# Hooly_2_023.net
KiCad netlist of a schematic drawn in EAGLE
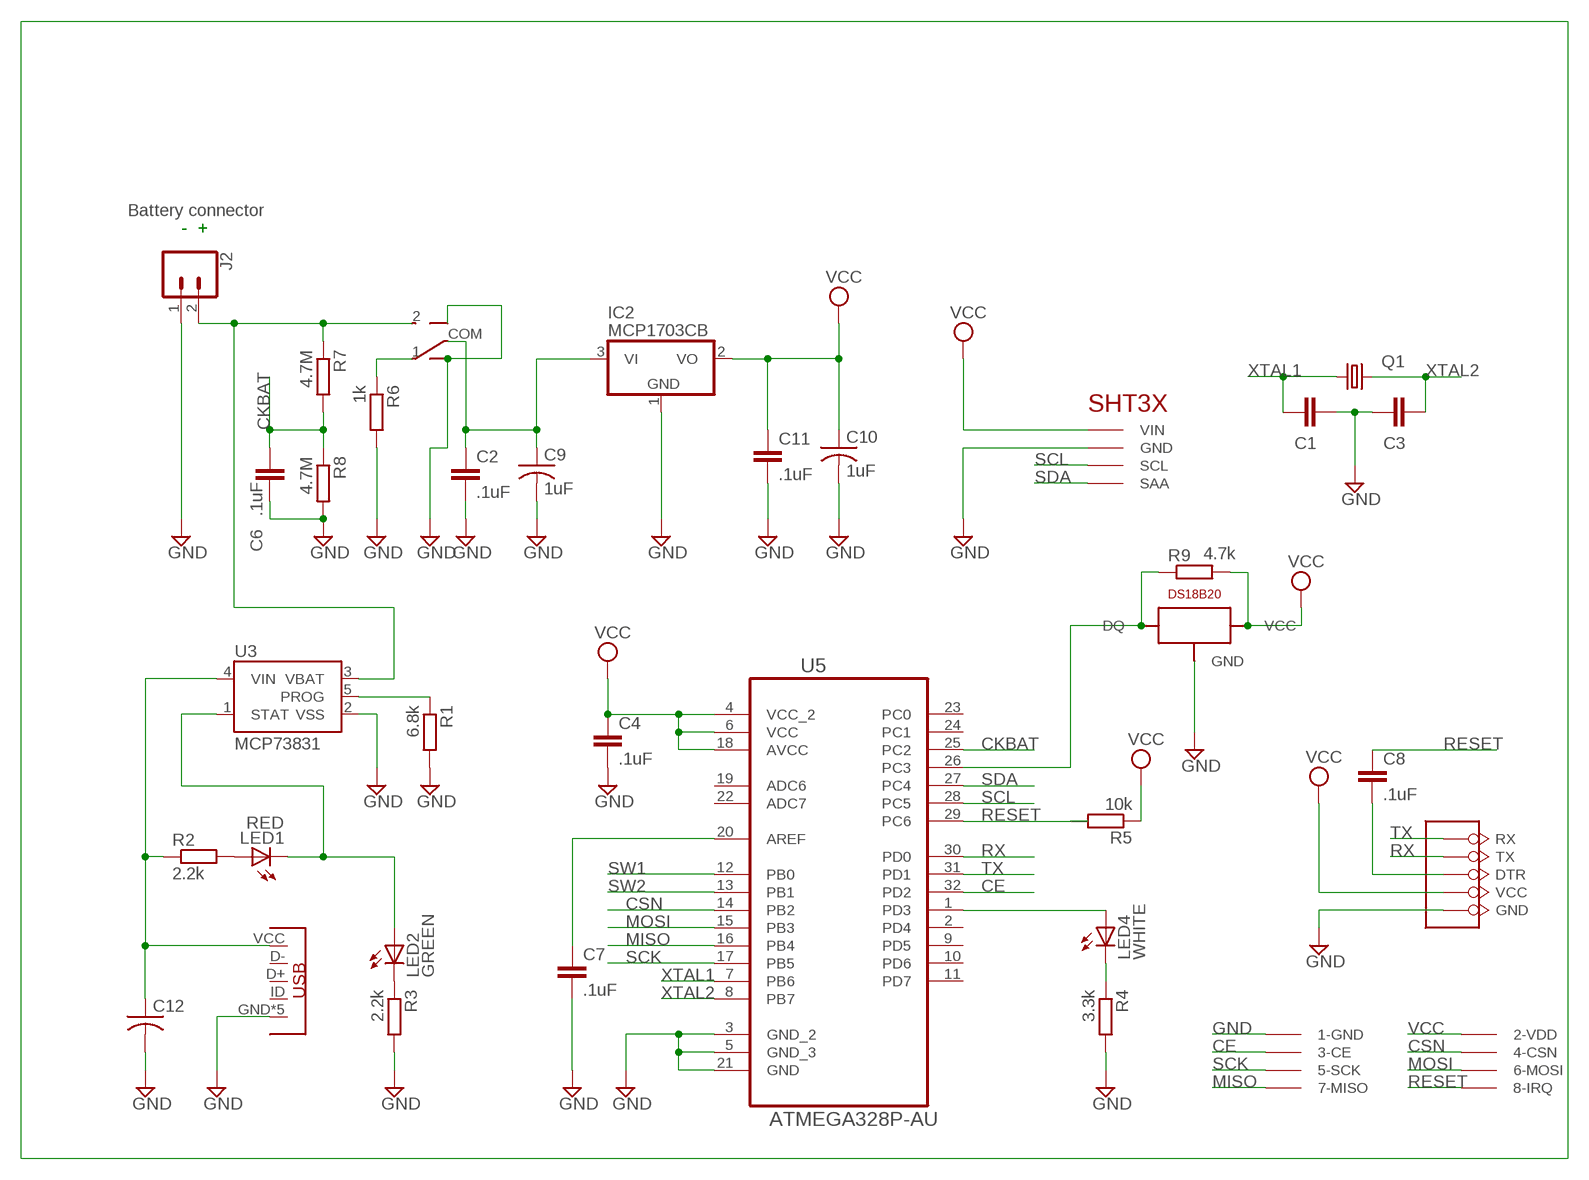
[diagram p0: schematic, sheet 1]

(export (version "E")
  (design (tool "Eeschema 10.0.6"))
  (components
    (comp (ref "C1")
      (value "C-EUC0603K")
      (footprint "eagle-import:C0603K")
      (libsource (lib "eagle-import") (part "C-EUC0603K"))
    )
    (comp (ref "C2")
      (value ".1uF")
      (footprint "eagle-import:C0603")
      (libsource (lib "eagle-import") (part "resistor_348_C-EUC0603"))
    )
    (comp (ref "C3")
      (value "C-EUC0603K")
      (footprint "eagle-import:C0603K")
      (libsource (lib "eagle-import") (part "C-EUC0603K"))
    )
    (comp (ref "C4")
      (value ".1uF")
      (footprint "eagle-import:C0603")
      (libsource (lib "eagle-import") (part "resistor_348_C-EUC0603"))
    )
    (comp (ref "C6")
      (value ".1uF")
      (footprint "eagle-import:C0603")
      (libsource (lib "eagle-import") (part "resistor_348_C-EUC0603"))
    )
    (comp (ref "C7")
      (value ".1uF")
      (footprint "eagle-import:C0603")
      (libsource (lib "eagle-import") (part "resistor_348_C-EUC0603"))
    )
    (comp (ref "C8")
      (value ".1uF")
      (footprint "eagle-import:C0603")
      (libsource (lib "eagle-import") (part "resistor_348_C-EUC0603"))
    )
    (comp (ref "C9")
      (value "1uF")
      (footprint "eagle-import:C1206K")
      (libsource (lib "eagle-import") (part "C-USC1206K"))
    )
    (comp (ref "C10")
      (value "1uF")
      (footprint "eagle-import:C1206K")
      (libsource (lib "eagle-import") (part "C-USC1206K"))
    )
    (comp (ref "C11")
      (value ".1uF")
      (footprint "eagle-import:C0603")
      (libsource (lib "eagle-import") (part "resistor_348_C-EUC0603"))
    )
    (comp (ref "C12")
      (value "C-USC1206K")
      (footprint "eagle-import:C1206K")
      (libsource (lib "eagle-import") (part "C-USC1206K"))
    )
    (comp (ref "IC2")
      (value "MCP1703CB")
      (footprint "eagle-import:SOT23")
      (libsource (lib "eagle-import") (part "MCP1703CB"))
    )
    (comp (ref "J2")
      (value "CONN_02")
      (footprint "eagle-import:1X02")
      (libsource (lib "eagle-import") (part "CONN_02"))
    )
    (comp (ref "LED1")
      (value "RED")
      (footprint "eagle-import:CHIPLED_0603")
      (libsource (lib "eagle-import") (part "LEDCHIPLED_0603"))
    )
    (comp (ref "LED2")
      (value "GREEN")
      (footprint "eagle-import:CHIPLED_0603")
      (libsource (lib "eagle-import") (part "LEDCHIPLED_0603"))
    )
    (comp (ref "LED4")
      (value "WHITE")
      (footprint "eagle-import:CHIPLED_0603")
      (libsource (lib "eagle-import") (part "LEDCHIPLED_0603"))
    )
    (comp (ref "Q1")
      (value "KX-9B")
      (footprint "eagle-import:5.0X3.2_2")
      (libsource (lib "eagle-import") (part "KX-9B"))
    )
    (comp (ref "R1")
      (value "6.8k")
      (footprint "eagle-import:R0603")
      (libsource (lib "eagle-import") (part "R-EU_R0603"))
    )
    (comp (ref "R2")
      (value "2.2k")
      (footprint "eagle-import:R0603")
      (libsource (lib "eagle-import") (part "R-EU_R0603"))
    )
    (comp (ref "R3")
      (value "2.2k")
      (footprint "eagle-import:R0603")
      (libsource (lib "eagle-import") (part "R-EU_R0603"))
    )
    (comp (ref "R4")
      (value "3.3k")
      (footprint "eagle-import:R0603")
      (libsource (lib "eagle-import") (part "R-EU_R0603"))
    )
    (comp (ref "R5")
      (value "10k")
      (footprint "eagle-import:R0603")
      (libsource (lib "eagle-import") (part "R-EU_R0603"))
    )
    (comp (ref "R6")
      (value "1k")
      (footprint "eagle-import:R0603")
      (libsource (lib "eagle-import") (part "R-EU_R0603"))
    )
    (comp (ref "R7")
      (value "4.7M")
      (footprint "eagle-import:R0603")
      (libsource (lib "eagle-import") (part "R-EU_R0603"))
    )
    (comp (ref "R8")
      (value "4.7M")
      (footprint "eagle-import:R0603")
      (libsource (lib "eagle-import") (part "R-EU_R0603"))
    )
    (comp (ref "R9")
      (value "4.7k")
      (footprint "eagle-import:R0603")
      (libsource (lib "eagle-import") (part "R-EU_R0603"))
    )
    (comp (ref "U$1")
      (value "SHT3XLARGE")
      (footprint "eagle-import:MYSHT3X")
      (libsource (lib "eagle-import") (part "SHT3XLARGE"))
    )
    (comp (ref "U$2")
      (value "MYSWITCH2MM")
      (footprint "eagle-import:MYSWITCH")
      (libsource (lib "eagle-import") (part "MYSWITCH2MM"))
    )
    (comp (ref "U$3")
      (value "MYDS18B20")
      (footprint "eagle-import:MYDS18B20")
      (libsource (lib "eagle-import") (part "MYDS18B20"))
    )
    (comp (ref "U$4")
      (value "MYNRF24L01SOCKET")
      (footprint "eagle-import:MYNRF24L01SOCKET")
      (libsource (lib "eagle-import") (part "MYNRF24L01SOCKET"))
    )
    (comp (ref "U$6")
      (value "FTDI232")
      (footprint "eagle-import:FTDI232")
      (libsource (lib "eagle-import") (part "FTDI232"))
    )
    (comp (ref "U$7")
      (value "MYMICROUSB")
      (footprint "eagle-import:MYMICROUSB")
      (libsource (lib "eagle-import") (part "MYMICROUSB"))
    )
    (comp (ref "U3")
      (value "MCP73831")
      (footprint "eagle-import:SOT23-5")
      (libsource (lib "eagle-import") (part "MCP73831"))
    )
    (comp (ref "U5")
      (value "ATMEGA328P-AU")
      (footprint "eagle-import:QFP80P900X900X120-32N")
      (libsource (lib "eagle-import") (part "ATMEGA328P-AU"))
    )
  )
  (nets
    (net (code "1") (name "/CE") (class "Default")
      (node (ref "U$4") (pin "CE") (pinfunction "3-CE_CE") (pintype "bidirectional"))
      (node (ref "U5") (pin "32") (pinfunction "PD2_32") (pintype "bidirectional"))
    )
    (net (code "2") (name "/CKBAT") (class "Default")
      (node (ref "C6") (pin "1") (pinfunction "1_1") (pintype "passive"))
      (node (ref "R7") (pin "2") (pinfunction "2_2") (pintype "passive"))
      (node (ref "R8") (pin "1") (pinfunction "1_1") (pintype "passive"))
      (node (ref "U5") (pin "25") (pinfunction "PC2_25") (pintype "bidirectional"))
    )
    (net (code "3") (name "/CSN") (class "Default")
      (node (ref "U$4") (pin "CSN") (pinfunction "4-CSN_CSN") (pintype "bidirectional"))
      (node (ref "U5") (pin "14") (pinfunction "PB2_14") (pintype "bidirectional"))
    )
    (net (code "4") (name "/MISO") (class "Default")
      (node (ref "U$4") (pin "MISO") (pinfunction "7-MISO_MISO") (pintype "bidirectional"))
      (node (ref "U5") (pin "16") (pinfunction "PB4_16") (pintype "bidirectional"))
    )
    (net (code "5") (name "/MOSI") (class "Default")
      (node (ref "U$4") (pin "MOSI") (pinfunction "6-MOSI_MOSI") (pintype "bidirectional"))
      (node (ref "U5") (pin "15") (pinfunction "PB3_15") (pintype "bidirectional"))
    )
    (net (code "6") (name "/RESET") (class "Default")
      (node (ref "C8") (pin "1") (pinfunction "1_1") (pintype "passive"))
      (node (ref "R5") (pin "2") (pinfunction "2_2") (pintype "passive"))
      (node (ref "U$4") (pin "IRQ") (pinfunction "8-IRQ_IRQ") (pintype "bidirectional"))
      (node (ref "U5") (pin "29") (pinfunction "PC6_29") (pintype "bidirectional"))
    )
    (net (code "7") (name "/RX") (class "Default")
      (node (ref "U$6") (pin "TX") (pinfunction "TX_TX") (pintype "bidirectional"))
      (node (ref "U5") (pin "30") (pinfunction "PD0_30") (pintype "bidirectional"))
    )
    (net (code "8") (name "/SCK") (class "Default")
      (node (ref "U$4") (pin "SCK") (pinfunction "5-SCK_SCK") (pintype "bidirectional"))
      (node (ref "U5") (pin "17") (pinfunction "PB5_17") (pintype "bidirectional"))
    )
    (net (code "9") (name "/SCL") (class "Default")
      (node (ref "U$1") (pin "SCL") (pinfunction "SCL_SCL") (pintype "bidirectional"))
      (node (ref "U5") (pin "28") (pinfunction "PC5_28") (pintype "bidirectional"))
    )
    (net (code "10") (name "/SDA") (class "Default")
      (node (ref "U$1") (pin "SAA") (pinfunction "SAA_SAA") (pintype "bidirectional"))
      (node (ref "U5") (pin "27") (pinfunction "PC4_27") (pintype "bidirectional"))
    )
    (net (code "11") (name "/SW1") (class "Default")
      (node (ref "U5") (pin "12") (pinfunction "PB0_12") (pintype "bidirectional"))
    )
    (net (code "12") (name "/SW2") (class "Default")
      (node (ref "U5") (pin "13") (pinfunction "PB1_13") (pintype "bidirectional"))
    )
    (net (code "13") (name "/TX") (class "Default")
      (node (ref "U$6") (pin "RX") (pinfunction "RX_RX") (pintype "bidirectional"))
      (node (ref "U5") (pin "31") (pinfunction "PD1_31") (pintype "bidirectional"))
    )
    (net (code "14") (name "/XTAL1") (class "Default")
      (node (ref "C1") (pin "1") (pinfunction "1_1") (pintype "passive"))
      (node (ref "Q1") (pin "1") (pinfunction "1_1") (pintype "passive"))
      (node (ref "U5") (pin "7") (pinfunction "PB6_7") (pintype "bidirectional"))
    )
    (net (code "15") (name "/XTAL2") (class "Default")
      (node (ref "C3") (pin "2") (pinfunction "2_2") (pintype "passive"))
      (node (ref "Q1") (pin "2") (pinfunction "2_2") (pintype "passive"))
      (node (ref "U5") (pin "8") (pinfunction "PB7_8") (pintype "bidirectional"))
    )
    (net (code "16") (name "GND") (class "Default")
      (node (ref "C1") (pin "2") (pinfunction "2_2") (pintype "passive"))
      (node (ref "C10") (pin "2") (pinfunction "2_2") (pintype "passive"))
      (node (ref "C11") (pin "2") (pinfunction "2_2") (pintype "passive"))
      (node (ref "C12") (pin "2") (pinfunction "2_2") (pintype "passive"))
      (node (ref "C2") (pin "2") (pinfunction "2_2") (pintype "passive"))
      (node (ref "C3") (pin "1") (pinfunction "1_1") (pintype "passive"))
      (node (ref "C4") (pin "2") (pinfunction "2_2") (pintype "passive"))
      (node (ref "C6") (pin "2") (pinfunction "2_2") (pintype "passive"))
      (node (ref "C7") (pin "2") (pinfunction "2_2") (pintype "passive"))
      (node (ref "C9") (pin "2") (pinfunction "2_2") (pintype "passive"))
      (node (ref "IC2") (pin "1") (pinfunction "GND_1") (pintype "passive"))
      (node (ref "J2") (pin "1") (pinfunction "1_1") (pintype "passive"))
      (node (ref "R1") (pin "2") (pinfunction "2_2") (pintype "passive"))
      (node (ref "R3") (pin "2") (pinfunction "2_2") (pintype "passive"))
      (node (ref "R4") (pin "2") (pinfunction "2_2") (pintype "passive"))
      (node (ref "R6") (pin "2") (pinfunction "2_2") (pintype "passive"))
      (node (ref "R8") (pin "2") (pinfunction "2_2") (pintype "passive"))
      (node (ref "U$1") (pin "GND") (pinfunction "GND_GND") (pintype "bidirectional"))
      (node (ref "U$2") (pin "GND1") (pinfunction "GND1_GND1") (pintype "bidirectional"))
      (node (ref "U$2") (pin "GND2") (pinfunction "GND2_GND2") (pintype "bidirectional"))
      (node (ref "U$3") (pin "GND") (pinfunction "GND_GND") (pintype "bidirectional"))
      (node (ref "U$4") (pin "GND") (pinfunction "1-GND_GND") (pintype "bidirectional"))
      (node (ref "U$6") (pin "GND") (pinfunction "GND_GND") (pintype "bidirectional"))
      (node (ref "U$7") (pin "GND") (pinfunction "GND_GND") (pintype "bidirectional"))
      (node (ref "U$7") (pin "P$6") (pinfunction "GND_P$6") (pintype "bidirectional"))
      (node (ref "U$7") (pin "P$7") (pinfunction "GND_P$7") (pintype "bidirectional"))
      (node (ref "U$7") (pin "P$8") (pinfunction "GND_P$8") (pintype "bidirectional"))
      (node (ref "U$7") (pin "P$9") (pinfunction "GND_P$9") (pintype "bidirectional"))
      (node (ref "U3") (pin "2") (pinfunction "VSS_2") (pintype "power_in"))
      (node (ref "U5") (pin "21") (pinfunction "GND_21") (pintype "passive"))
      (node (ref "U5") (pin "3") (pinfunction "GND_2_3") (pintype "passive"))
      (node (ref "U5") (pin "5") (pinfunction "GND_3_5") (pintype "passive"))
    )
    (net (code "17") (name "Net-(C8-Pad2)") (class "Default")
      (node (ref "C8") (pin "2") (pinfunction "2_2") (pintype "passive"))
      (node (ref "U$6") (pin "DTR") (pinfunction "DTR_DTR") (pintype "bidirectional"))
    )
    (net (code "18") (name "Net-(IC2-VI)") (class "Default")
      (node (ref "C2") (pin "1") (pinfunction "1_1") (pintype "passive"))
      (node (ref "C9") (pin "1") (pinfunction "1_1") (pintype "passive"))
      (node (ref "IC2") (pin "3") (pinfunction "VI_3") (pintype "input"))
      (node (ref "U$2") (pin "COM") (pinfunction "COM_COM") (pintype "bidirectional"))
    )
    (net (code "19") (name "Net-(LED1-PadA)") (class "Default")
      (node (ref "LED1") (pin "A") (pinfunction "A_A") (pintype "passive"))
      (node (ref "R2") (pin "2") (pinfunction "2_2") (pintype "passive"))
    )
    (net (code "20") (name "Net-(LED2-PadC)") (class "Default")
      (node (ref "LED2") (pin "C") (pinfunction "C_C") (pintype "passive"))
      (node (ref "R3") (pin "1") (pinfunction "1_1") (pintype "passive"))
    )
    (net (code "21") (name "Net-(LED4-PadC)") (class "Default")
      (node (ref "LED4") (pin "C") (pinfunction "C_C") (pintype "passive"))
      (node (ref "R4") (pin "1") (pinfunction "1_1") (pintype "passive"))
    )
    (net (code "22") (name "Net-(R6-Pad1)") (class "Default")
      (node (ref "R6") (pin "1") (pinfunction "1_1") (pintype "passive"))
      (node (ref "U$2") (pin "1") (pinfunction "1_1") (pintype "bidirectional"))
    )
    (net (code "23") (name "Net-(U3-PROG)") (class "Default")
      (node (ref "R1") (pin "1") (pinfunction "1_1") (pintype "passive"))
      (node (ref "U3") (pin "5") (pinfunction "PROG_5") (pintype "input"))
    )
    (net (code "24") (name "Net-(U3-STAT)") (class "Default")
      (node (ref "LED1") (pin "C") (pinfunction "C_C") (pintype "passive"))
      (node (ref "LED2") (pin "A") (pinfunction "A_A") (pintype "passive"))
      (node (ref "U3") (pin "1") (pinfunction "STAT_1") (pintype "output"))
    )
    (net (code "25") (name "Net-(U3-VBAT)") (class "Default")
      (node (ref "J2") (pin "2") (pinfunction "2_2") (pintype "passive"))
      (node (ref "R7") (pin "1") (pinfunction "1_1") (pintype "passive"))
      (node (ref "U$2") (pin "2") (pinfunction "2_2") (pintype "bidirectional"))
      (node (ref "U3") (pin "3") (pinfunction "VBAT_3") (pintype "power_in"))
    )
    (net (code "26") (name "Net-(U3-VIN)") (class "Default")
      (node (ref "C12") (pin "1") (pinfunction "1_1") (pintype "passive"))
      (node (ref "R2") (pin "1") (pinfunction "1_1") (pintype "passive"))
      (node (ref "U$7") (pin "VCC") (pinfunction "VCC_VCC") (pintype "bidirectional"))
      (node (ref "U3") (pin "4") (pinfunction "VIN_4") (pintype "power_in"))
    )
    (net (code "27") (name "Net-(U5-AREF)") (class "Default")
      (node (ref "C7") (pin "1") (pinfunction "1_1") (pintype "passive"))
      (node (ref "U5") (pin "20") (pinfunction "AREF_20") (pintype "input"))
    )
    (net (code "28") (name "Net-(U5-PC3)") (class "Default")
      (node (ref "R9") (pin "1") (pinfunction "1_1") (pintype "passive"))
      (node (ref "U$3") (pin "DQ") (pinfunction "DQ_DQ") (pintype "bidirectional"))
      (node (ref "U5") (pin "26") (pinfunction "PC3_26") (pintype "bidirectional"))
    )
    (net (code "29") (name "Net-(U5-PD3)") (class "Default")
      (node (ref "LED4") (pin "A") (pinfunction "A_A") (pintype "passive"))
      (node (ref "U5") (pin "1") (pinfunction "PD3_1") (pintype "bidirectional"))
    )
    (net (code "30") (name "VCC") (class "Default")
      (node (ref "C10") (pin "1") (pinfunction "1_1") (pintype "passive"))
      (node (ref "C11") (pin "1") (pinfunction "1_1") (pintype "passive"))
      (node (ref "C4") (pin "1") (pinfunction "1_1") (pintype "passive"))
      (node (ref "IC2") (pin "2") (pinfunction "VO_2") (pintype "passive"))
      (node (ref "R5") (pin "1") (pinfunction "1_1") (pintype "passive"))
      (node (ref "R9") (pin "2") (pinfunction "2_2") (pintype "passive"))
      (node (ref "U$1") (pin "VIN") (pinfunction "VIN_VIN") (pintype "bidirectional"))
      (node (ref "U$3") (pin "VCC") (pinfunction "VCC_VCC") (pintype "bidirectional"))
      (node (ref "U$4") (pin "VDD") (pinfunction "2-VDD_VDD") (pintype "bidirectional"))
      (node (ref "U$6") (pin "VCC") (pinfunction "VCC_VCC") (pintype "bidirectional"))
      (node (ref "U5") (pin "18") (pinfunction "AVCC_18") (pintype "power_in"))
      (node (ref "U5") (pin "4") (pinfunction "VCC_2_4") (pintype "power_in"))
      (node (ref "U5") (pin "6") (pinfunction "VCC_6") (pintype "power_in"))
    )
    (net (code "31") (name "unconnected-(U$7-PadD+)") (class "Default")
      (node (ref "U$7") (pin "D+") (pinfunction "D+_D+") (pintype "bidirectional"))
    )
    (net (code "32") (name "unconnected-(U$7-PadD-)") (class "Default")
      (node (ref "U$7") (pin "D-") (pinfunction "D-_D-") (pintype "bidirectional"))
    )
    (net (code "33") (name "unconnected-(U$7-PadID)") (class "Default")
      (node (ref "U$7") (pin "ID") (pinfunction "ID_ID") (pintype "bidirectional"))
    )
    (net (code "34") (name "unconnected-(U5-ADC6-Pad19)") (class "Default")
      (node (ref "U5") (pin "19") (pinfunction "ADC6_19") (pintype "input"))
    )
    (net (code "35") (name "unconnected-(U5-ADC7-Pad22)") (class "Default")
      (node (ref "U5") (pin "22") (pinfunction "ADC7_22") (pintype "input"))
    )
    (net (code "36") (name "unconnected-(U5-PC0-Pad23)") (class "Default")
      (node (ref "U5") (pin "23") (pinfunction "PC0_23") (pintype "bidirectional"))
    )
    (net (code "37") (name "unconnected-(U5-PC1-Pad24)") (class "Default")
      (node (ref "U5") (pin "24") (pinfunction "PC1_24") (pintype "bidirectional"))
    )
    (net (code "38") (name "unconnected-(U5-PD4-Pad2)") (class "Default")
      (node (ref "U5") (pin "2") (pinfunction "PD4_2") (pintype "bidirectional"))
    )
    (net (code "39") (name "unconnected-(U5-PD5-Pad9)") (class "Default")
      (node (ref "U5") (pin "9") (pinfunction "PD5_9") (pintype "bidirectional"))
    )
    (net (code "40") (name "unconnected-(U5-PD6-Pad10)") (class "Default")
      (node (ref "U5") (pin "10") (pinfunction "PD6_10") (pintype "bidirectional"))
    )
    (net (code "41") (name "unconnected-(U5-PD7-Pad11)") (class "Default")
      (node (ref "U5") (pin "11") (pinfunction "PD7_11") (pintype "bidirectional"))
    )
  )
)
